# ETAG_v9_3b_EM4095.net
KiCad netlist of a schematic drawn in EAGLE
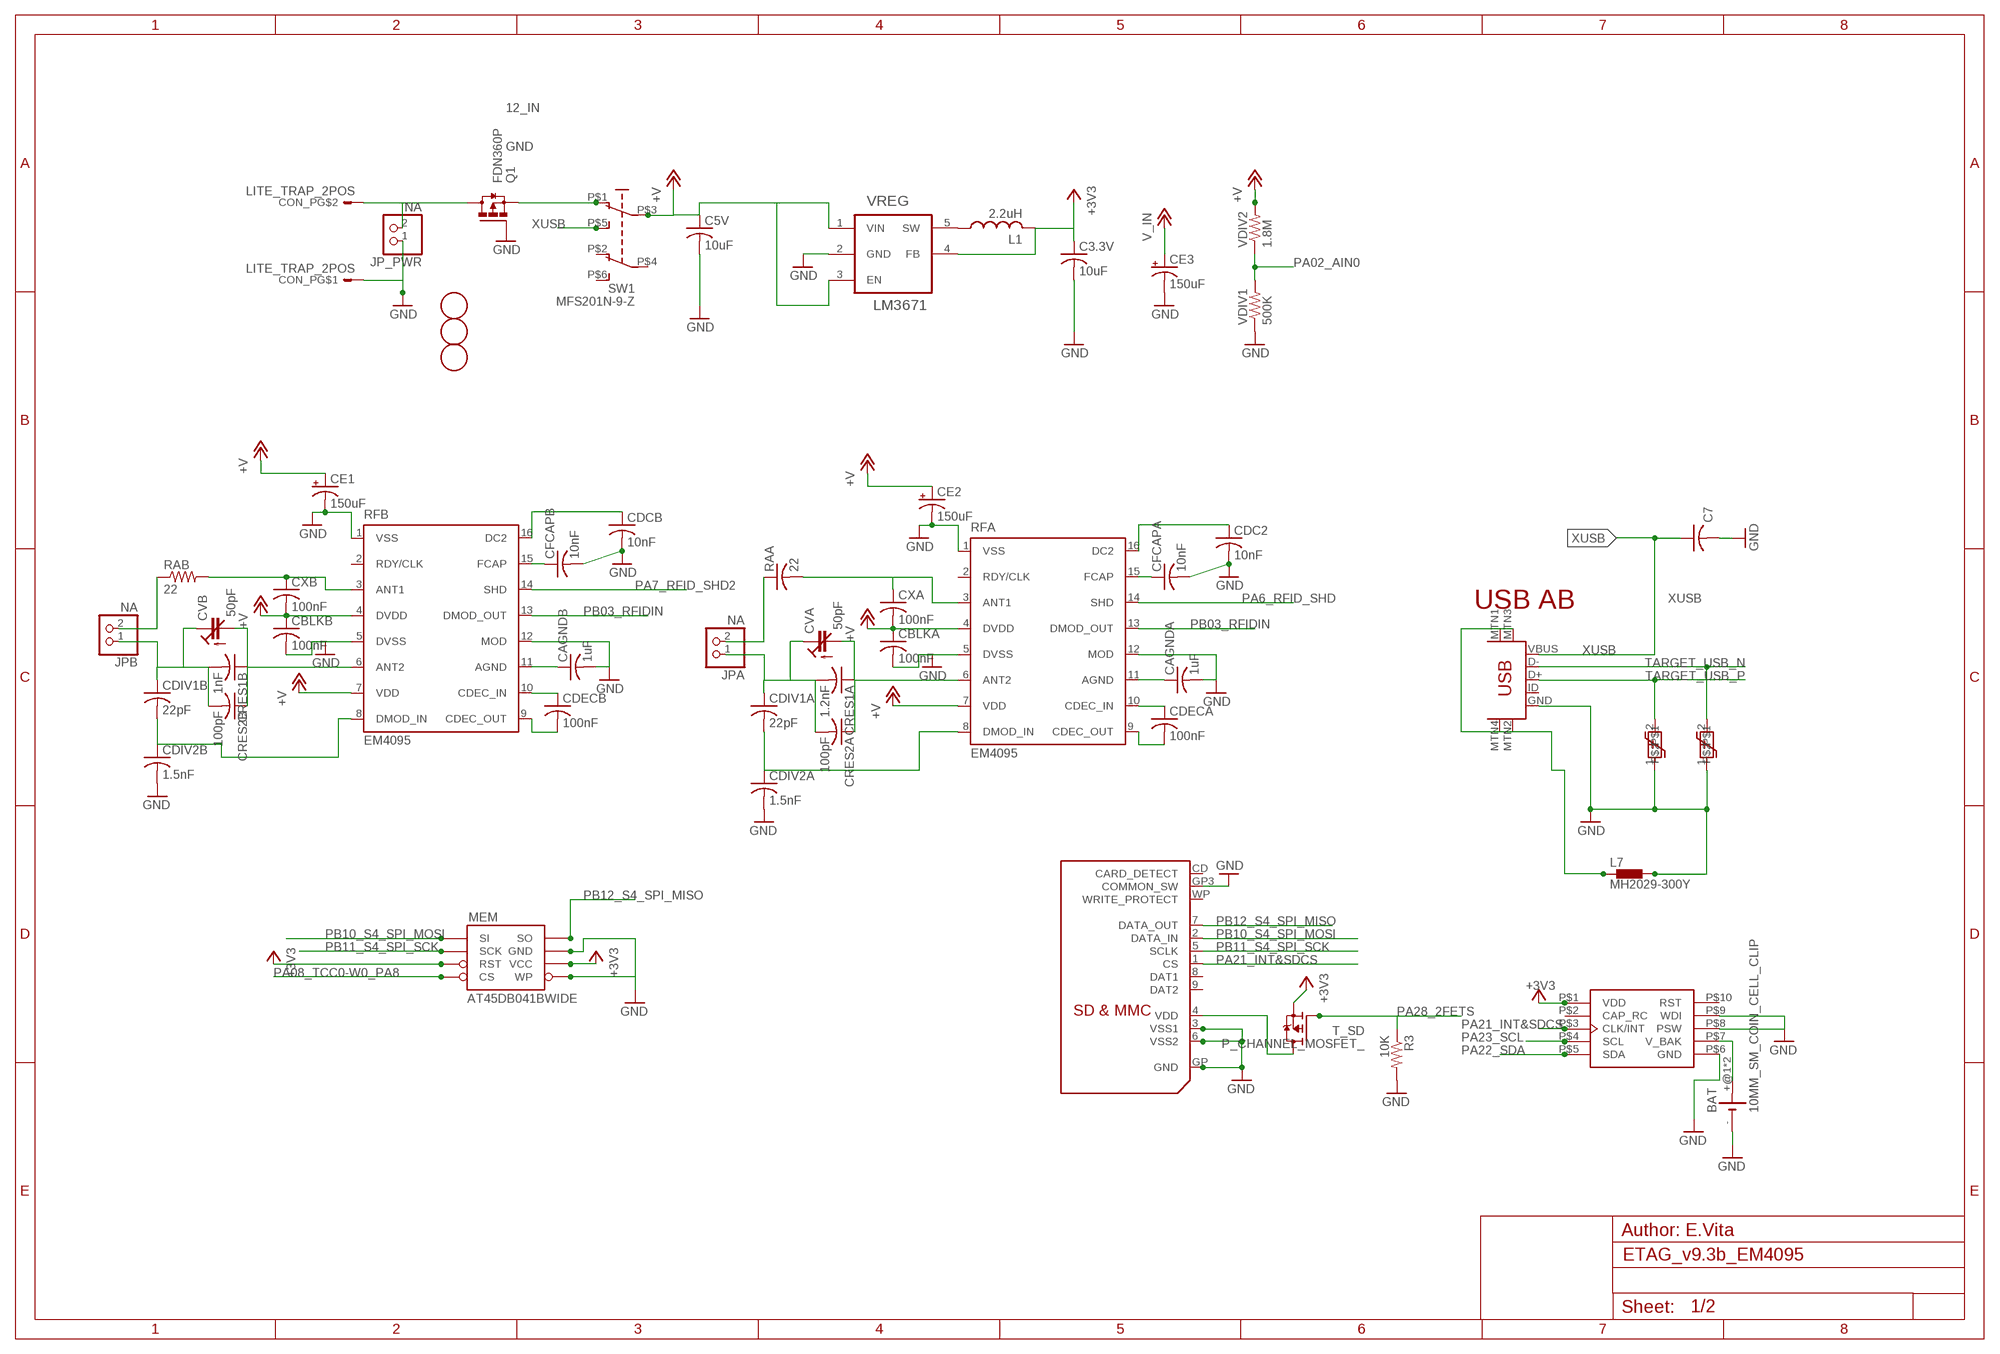
[diagram p0: schematic, sheet 1]
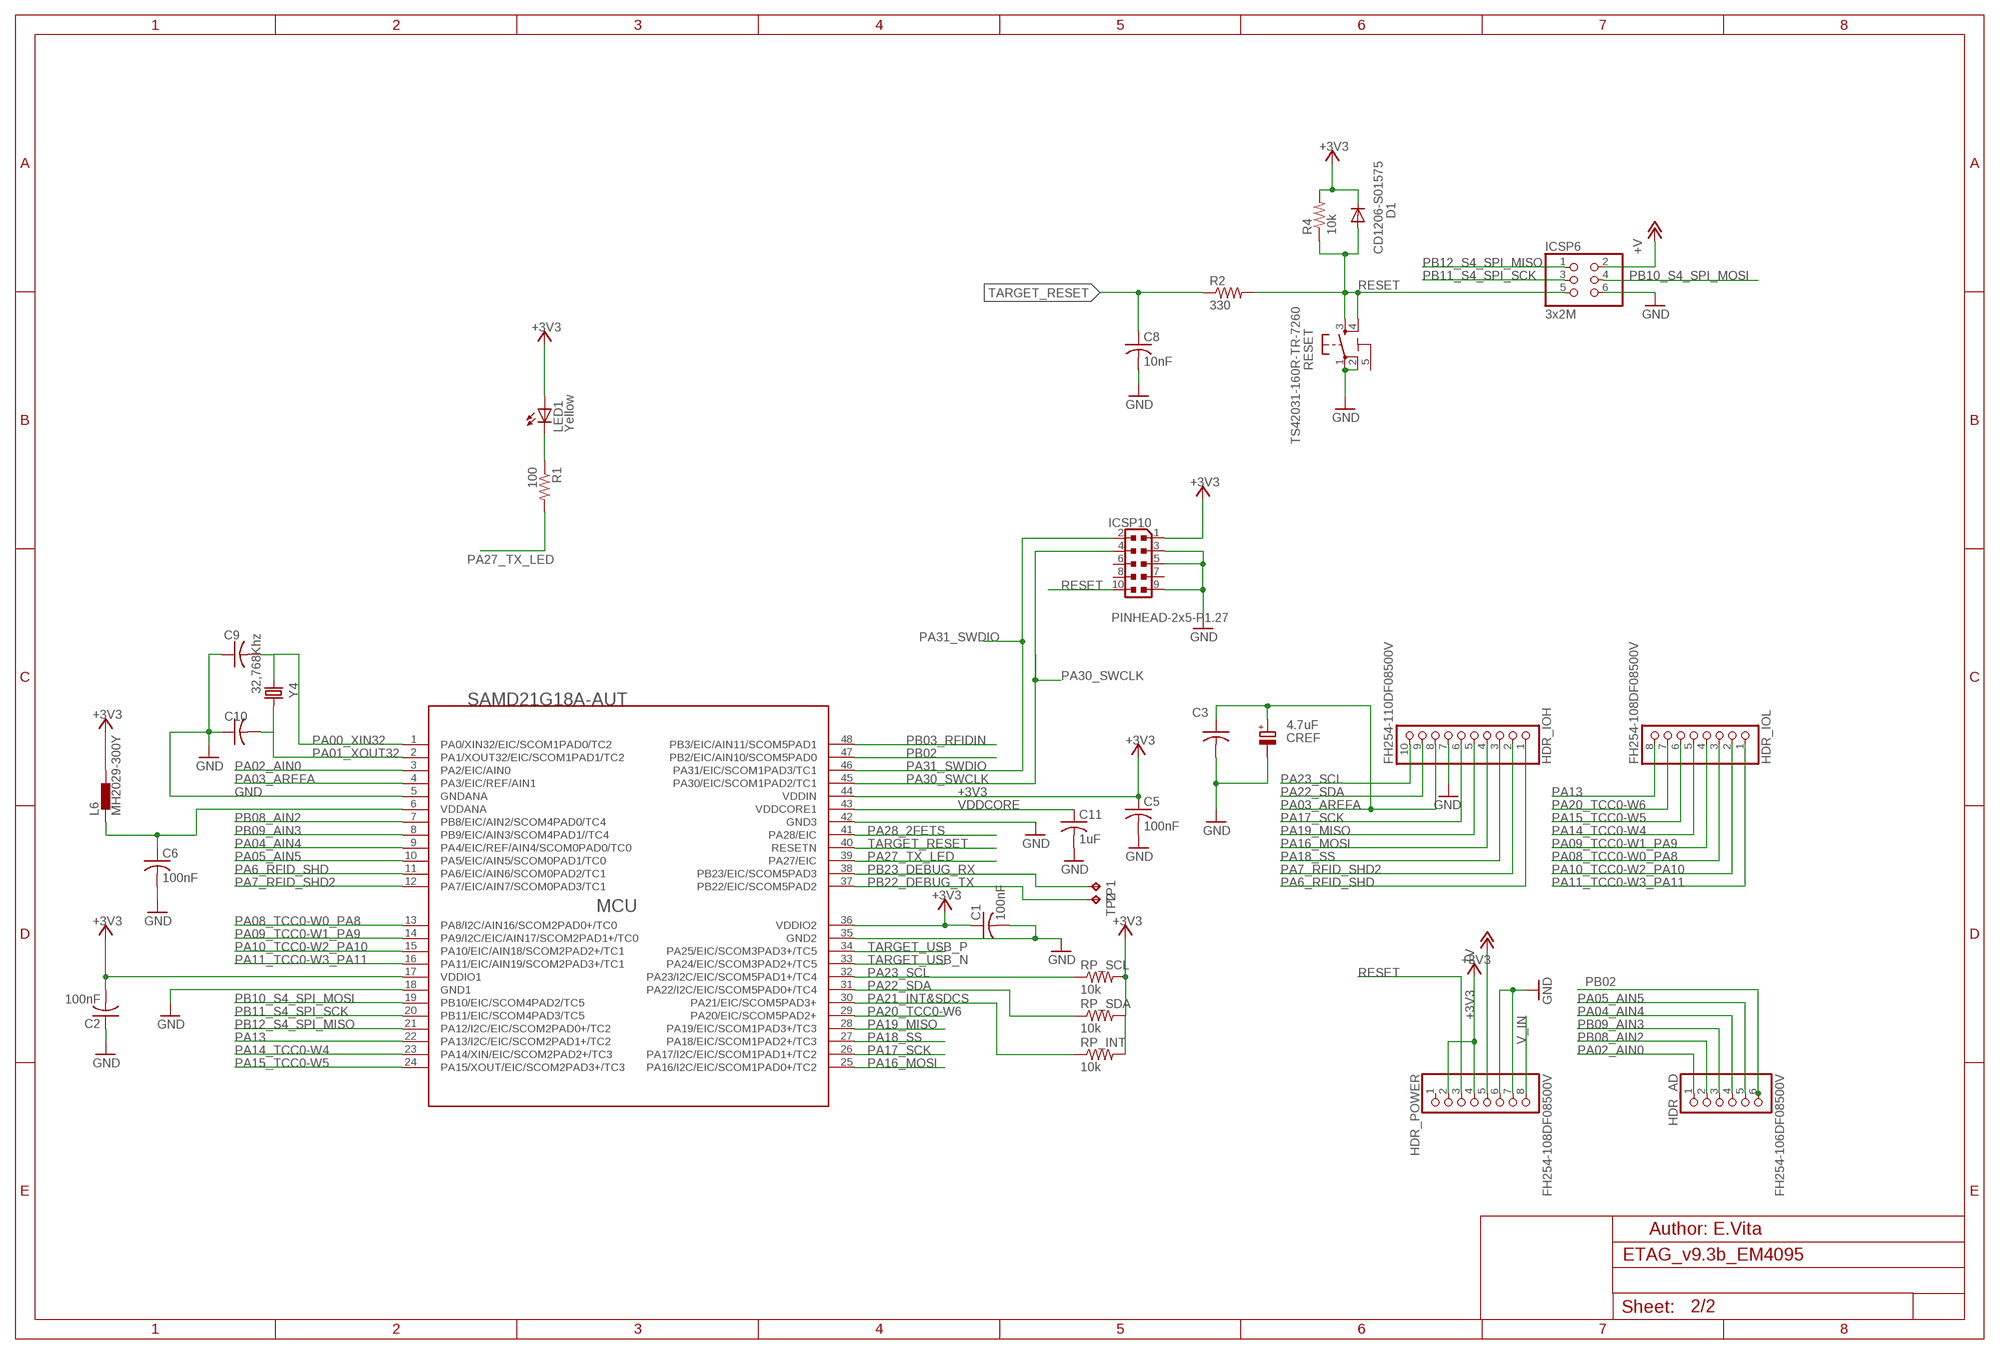
[diagram p1: schematic, sheet 2]

(export (version "E")
  (design (tool "Eeschema 10.0.6"))
  (components
    (comp (ref "C1")
      (value "100nF")
      (footprint "eagle-import:C0603-ROUND")
      (libsource (lib "eagle-import") (part "C-USROUND"))
    )
    (comp (ref "C2")
      (value "100nF")
      (footprint "eagle-import:C0603-ROUND")
      (libsource (lib "eagle-import") (part "C-USROUND"))
    )
    (comp (ref "C3")
      (value "100nF")
      (footprint "eagle-import:C0603-ROUND")
      (libsource (lib "eagle-import") (part "C-USROUND"))
    )
    (comp (ref "C5")
      (value "100nF")
      (footprint "eagle-import:C0603-ROUND")
      (libsource (lib "eagle-import") (part "C-USROUND"))
    )
    (comp (ref "C6")
      (value "100nF")
      (footprint "eagle-import:C0603-ROUND")
      (libsource (lib "eagle-import") (part "C-USROUND"))
    )
    (comp (ref "C8")
      (value "10nF")
      (footprint "eagle-import:C0603-ROUND")
      (libsource (lib "eagle-import") (part "C-USROUND"))
    )
    (comp (ref "C9")
      (value "22pF")
      (footprint "eagle-import:C0603-ROUND")
      (libsource (lib "eagle-import") (part "C-USROUND"))
    )
    (comp (ref "C10")
      (value "22pF")
      (footprint "eagle-import:C0603-ROUND")
      (libsource (lib "eagle-import") (part "C-USROUND"))
    )
    (comp (ref "C11")
      (value "1uF")
      (footprint "eagle-import:C0603-ROUND")
      (libsource (lib "eagle-import") (part "C-USROUND"))
    )
    (comp (ref "CREF")
      (value "4.7uF")
      (footprint "eagle-import:SMC_A")
      (fields (field (name "PART_NUMBER") "TAJA475M016RNJ"))
      (libsource (lib "eagle-import") (part "0474_TAJA475M016RNJ"))
    )
    (comp (ref "D1")
      (value "CD1206-S01575")
      (footprint "eagle-import:MINIMELF")
      (libsource (lib "eagle-import") (part "0012_CD1206-S01575"))
    )
    (comp (ref "HDR_AD")
      (value "FH254-106DF08500V")
      (footprint "eagle-import:1X06")
      (fields (field (name "PART_NUMBER") "20TW-535"))
      (libsource (lib "eagle-import") (part "1682_20TW-535_STD"))
    )
    (comp (ref "HDR_IOH")
      (value "FH254-110DF08500V")
      (footprint "eagle-import:1X10")
      (fields (field (name "PART_NUMBER") "20TW-537"))
      (libsource (lib "eagle-import") (part "1684_20TW-537"))
    )
    (comp (ref "HDR_IOL")
      (value "FH254-108DF08500V")
      (footprint "eagle-import:1X08")
      (fields (field (name "PART_NUMBER") "20TW-536"))
      (libsource (lib "eagle-import") (part "1683_20TW-536"))
    )
    (comp (ref "HDR_POWER")
      (value "FH254-108DF08500V")
      (footprint "eagle-import:1X08")
      (fields (field (name "PART_NUMBER") "20TW-536"))
      (libsource (lib "eagle-import") (part "1683_20TW-536"))
    )
    (comp (ref "ICSP6")
      (value "3x2M")
      (footprint "eagle-import:2X03")
      (fields (field (name "PART_NUMBER") "PH254-203DF118A00V"))
      (libsource (lib "eagle-import") (part "0114_PH254-203DF118A00V"))
    )
    (comp (ref "ICSP10")
      (value "PINHEAD-2x5-P1.27")
      (footprint "eagle-import:PINHEAD_2X05_127")
      (libsource (lib "eagle-import") (part "0171_PH127-205DF055G00AROUND-PADS"))
    )
    (comp (ref "L6")
      (value "MH2029-300Y")
      (footprint "eagle-import:C0805K")
      (libsource (lib "eagle-import") (part "BLM15H0805"))
    )
    (comp (ref "LED1")
      (value "Yellow")
      (footprint "eagle-import:CHIPLED_0805")
      (fields (field (name "PART_NUMBER") "KPT-2012YC"))
      (libsource (lib "eagle-import") (part "0044_KPT-2012YC"))
    )
    (comp (ref "MCU")
      (value "SAMD21G18A-AUT")
      (footprint "eagle-import:TQFP48-7X7")
      (libsource (lib "eagle-import") (part "1792_SAMD21G18A-AUT"))
    )
    (comp (ref "R1")
      (value "100")
      (footprint "eagle-import:C0603-ROUND")
      (libsource (lib "eagle-import") (part "R-US_ROUND"))
    )
    (comp (ref "R2")
      (value "330")
      (footprint "eagle-import:C0603-ROUND")
      (libsource (lib "eagle-import") (part "R-US_ROUND"))
    )
    (comp (ref "R4")
      (value "10k")
      (footprint "eagle-import:C0603-ROUND")
      (libsource (lib "eagle-import") (part "R-US_ROUND"))
    )
    (comp (ref "RESET")
      (value "TS42031-160R-TR-7260")
      (footprint "eagle-import:TS42")
      (fields (field (name "PART_NUMBER") "IT-1157AHNP-160G-G_GTR"))
      (libsource (lib "eagle-import") (part "0946_TS42031-160W-TR-7260"))
    )
    (comp (ref "RP_INT")
      (value "10k")
      (footprint "eagle-import:C0603-ROUND")
      (libsource (lib "eagle-import") (part "R-US_ROUND"))
    )
    (comp (ref "RP_SCL")
      (value "10k")
      (footprint "eagle-import:C0603-ROUND")
      (libsource (lib "eagle-import") (part "R-US_ROUND"))
    )
    (comp (ref "RP_SDA")
      (value "10k")
      (footprint "eagle-import:C0603-ROUND")
      (libsource (lib "eagle-import") (part "R-US_ROUND"))
    )
    (comp (ref "TP1")
      (value "TPTP15R")
      (footprint "eagle-import:TP15R")
      (libsource (lib "eagle-import") (part "TPTP15R"))
    )
    (comp (ref "TP2")
      (value "TPTP15R")
      (footprint "eagle-import:TP15R")
      (libsource (lib "eagle-import") (part "TPTP15R"))
    )
    (comp (ref "Y4")
      (value "32,768Khz")
      (footprint "eagle-import:RESONATOR_EPSON_FC_145")
      (fields (field (name "PART_NUMBER") "ABS07-32.768KHZ-T"))
      (libsource (lib "eagle-import") (part "0213_ABS07-32.768KHZ-T"))
    )
    (comp (ref "BAT")
      (value "10MM_SM_COIN_CELL_CLIP")
      (footprint "eagle-import:10MM_SM_COIN_CELL_CLIP")
      (libsource (lib "eagle-import") (part "10MM_SM_COIN_CELL_CLIP"))
    )
    (comp (ref "C3.3V")
      (value "10uF")
      (footprint "eagle-import:C0805")
      (libsource (lib "eagle-import") (part "C-USC0805"))
    )
    (comp (ref "C5V")
      (value "10uF")
      (footprint "eagle-import:C0805")
      (libsource (lib "eagle-import") (part "C-USC0805"))
    )
    (comp (ref "C7")
      (value "10nF")
      (footprint "eagle-import:C0603-ROUND")
      (libsource (lib "eagle-import") (part "C-USROUND"))
    )
    (comp (ref "CAGNDA")
      (value "1uF")
      (footprint "eagle-import:C0603-ROUND")
      (libsource (lib "eagle-import") (part "C-US"))
    )
    (comp (ref "CAGNDB")
      (value "1uF")
      (footprint "eagle-import:C0603-ROUND")
      (libsource (lib "eagle-import") (part "C-US"))
    )
    (comp (ref "CBLKA")
      (value "100nF")
      (footprint "eagle-import:C0603-ROUND")
      (libsource (lib "eagle-import") (part "C-US"))
    )
    (comp (ref "CBLKB")
      (value "100nF")
      (footprint "eagle-import:C0603-ROUND")
      (libsource (lib "eagle-import") (part "C-US"))
    )
    (comp (ref "CDC2")
      (value "10nF")
      (footprint "eagle-import:C0603-ROUND")
      (libsource (lib "eagle-import") (part "C-US"))
    )
    (comp (ref "CDCB")
      (value "10nF")
      (footprint "eagle-import:C0603-ROUND")
      (libsource (lib "eagle-import") (part "C-USROUND"))
    )
    (comp (ref "CDECA")
      (value "100nF")
      (footprint "eagle-import:C0603-ROUND")
      (libsource (lib "eagle-import") (part "C-US"))
    )
    (comp (ref "CDECB")
      (value "100nF")
      (footprint "eagle-import:C0603-ROUND")
      (libsource (lib "eagle-import") (part "C-US"))
    )
    (comp (ref "CDIV1A")
      (value "22pF")
      (footprint "eagle-import:C0603-ROUND")
      (libsource (lib "eagle-import") (part "C-US"))
    )
    (comp (ref "CDIV1B")
      (value "22pF")
      (footprint "eagle-import:C0603-ROUND")
      (libsource (lib "eagle-import") (part "C-US"))
    )
    (comp (ref "CDIV2A")
      (value "1.5nF")
      (footprint "eagle-import:C0603-ROUND")
      (libsource (lib "eagle-import") (part "C-USROUND"))
    )
    (comp (ref "CDIV2B")
      (value "1.5nF")
      (footprint "eagle-import:C0603-ROUND")
      (libsource (lib "eagle-import") (part "C-US"))
    )
    (comp (ref "CE1")
      (value "150uF")
      (footprint "eagle-import:E2-5")
      (libsource (lib "eagle-import") (part "CPOL-USE2-5"))
    )
    (comp (ref "CE2")
      (value "150uF")
      (footprint "eagle-import:E2-5")
      (libsource (lib "eagle-import") (part "CPOL-USE2-5"))
    )
    (comp (ref "CE3")
      (value "150uF")
      (footprint "eagle-import:E2-5")
      (libsource (lib "eagle-import") (part "CPOL-USE2-5"))
    )
    (comp (ref "CFCAPA")
      (value "10nF")
      (footprint "eagle-import:C0603-ROUND")
      (libsource (lib "eagle-import") (part "C-USROUND"))
    )
    (comp (ref "CFCAPB")
      (value "10nF")
      (footprint "eagle-import:C0603-ROUND")
      (libsource (lib "eagle-import") (part "C-US"))
    )
    (comp (ref "CON_P")
      (value "LITE_TRAP_2POS")
      (footprint "eagle-import:LITE_TRAP_MINI")
      (libsource (lib "eagle-import") (part "LITE_TRAP_2POS"))
    )
    (comp (ref "CRES1A")
      (value "1.2nF")
      (footprint "eagle-import:C0603-ROUND")
      (libsource (lib "eagle-import") (part "C-USROUND"))
    )
    (comp (ref "CRES1B")
      (value "1nF")
      (footprint "eagle-import:C0603-ROUND")
      (libsource (lib "eagle-import") (part "C-US"))
    )
    (comp (ref "CRES2A")
      (value "100pF")
      (footprint "eagle-import:C0603-ROUND")
      (libsource (lib "eagle-import") (part "C-US"))
    )
    (comp (ref "CRES2B")
      (value "100pF")
      (footprint "eagle-import:C0603-ROUND")
      (libsource (lib "eagle-import") (part "C-US"))
    )
    (comp (ref "CVA")
      (value "50pF")
      (footprint "eagle-import:CTRIM3018_11")
      (libsource (lib "eagle-import") (part "C-TRIMM3018_11"))
    )
    (comp (ref "CVB")
      (value "50pF")
      (footprint "eagle-import:CTRIM3018_11")
      (libsource (lib "eagle-import") (part "C-TRIMM3018_11"))
    )
    (comp (ref "CXA")
      (value "100nF")
      (footprint "eagle-import:C0603-ROUND")
      (libsource (lib "eagle-import") (part "C-US"))
    )
    (comp (ref "CXB")
      (value "100nF")
      (footprint "eagle-import:C0603-ROUND")
      (libsource (lib "eagle-import") (part "C-US"))
    )
    (comp (ref "FD1")
      (value "FIDUCIALMOUNT")
      (footprint "eagle-import:FIDUCIA-MOUNT")
      (libsource (lib "eagle-import") (part "FIDUCIALMOUNT"))
    )
    (comp (ref "FD2")
      (value "FIDUCIALMOUNT")
      (footprint "eagle-import:FIDUCIA-MOUNT")
      (libsource (lib "eagle-import") (part "FIDUCIALMOUNT"))
    )
    (comp (ref "FD3")
      (value "FIDUCIALMOUNT")
      (footprint "eagle-import:FIDUCIA-MOUNT")
      (libsource (lib "eagle-import") (part "FIDUCIALMOUNT"))
    )
    (comp (ref "JPA")
      (value "NA")
      (footprint "eagle-import:1X02")
      (libsource (lib "eagle-import") (part "PINHD-1X2"))
    )
    (comp (ref "JPB")
      (value "NA")
      (footprint "eagle-import:1X02")
      (libsource (lib "eagle-import") (part "PINHD-1X2"))
    )
    (comp (ref "JP_PWR")
      (value "NA")
      (footprint "eagle-import:1X02")
      (libsource (lib "eagle-import") (part "PINHD-1X2"))
    )
    (comp (ref "L1")
      (value "2.2uH")
      (footprint "eagle-import:SMT_COIL_INDUCTOR_4X4MM")
      (libsource (lib "eagle-import") (part "L-US4X4"))
    )
    (comp (ref "L7")
      (value "MH2029-300Y")
      (footprint "eagle-import:C0805K")
      (libsource (lib "eagle-import") (part "BLM15H0805"))
    )
    (comp (ref "MEM")
      (value "AT45DB041BWIDE")
      (footprint "eagle-import:SO08WIDE")
      (libsource (lib "eagle-import") (part "AT45DB041BWIDE"))
    )
    (comp (ref "Q1")
      (value "FDN360P")
      (footprint "eagle-import:SUPER-SOT3")
      (libsource (lib "eagle-import") (part "FDN360P"))
    )
    (comp (ref "R3")
      (value "10K")
      (footprint "eagle-import:C0603-ROUND")
      (libsource (lib "eagle-import") (part "R-US_ROUND"))
    )
    (comp (ref "RAA")
      (value "22")
      (footprint "eagle-import:C0805")
      (libsource (lib "eagle-import") (part "C-USC0805"))
    )
    (comp (ref "RAB")
      (value "22")
      (footprint "eagle-import:R0805")
      (libsource (lib "eagle-import") (part "R-US_R0805"))
    )
    (comp (ref "RFA")
      (value "EM4095")
      (footprint "eagle-import:SO16")
      (libsource (lib "eagle-import") (part "EM4095"))
    )
    (comp (ref "RFB")
      (value "EM4095")
      (footprint "eagle-import:SO16")
      (libsource (lib "eagle-import") (part "EM4095"))
    )
    (comp (ref "RTC")
      (value "MC-RTC-RV-1805-C3-I2C")
      (footprint "eagle-import:MC-RTC-C3")
      (libsource (lib "eagle-import") (part "MC-RTC-RV-1805-C3-I2C"))
    )
    (comp (ref "SD")
      (value "SDMMC06132")
      (footprint "eagle-import:06132")
      (libsource (lib "eagle-import") (part "SDMMC06132"))
    )
    (comp (ref "SW1")
      (value "MFS201N-9-Z")
      (footprint "eagle-import:MFS201N-9-Z")
      (libsource (lib "eagle-import") (part "MFS201N-9-Z"))
    )
    (comp (ref "T_SD")
      (value "P_CHANNEL_MOSFET_")
      (footprint "eagle-import:SOT23")
      (libsource (lib "eagle-import") (part "P_CHANNEL_MOSFET_"))
    )
    (comp (ref "USB")
      (value "USB-MINIB-5PIN")
      (footprint "eagle-import:USB-MINIB")
      (libsource (lib "eagle-import") (part "USB-MINIB-5PIN"))
    )
    (comp (ref "VDIV1")
      (value "500K")
      (footprint "eagle-import:C0603-ROUND")
      (libsource (lib "eagle-import") (part "R-US_ROUND"))
    )
    (comp (ref "VDIV2")
      (value "1.8M")
      (footprint "eagle-import:C0603-ROUND")
      (libsource (lib "eagle-import") (part "R-US_ROUND"))
    )
    (comp (ref "VREG")
      (value "LM3671")
      (footprint "eagle-import:SOT23-5L")
      (libsource (lib "eagle-import") (part "LM3671_SWITCHING_REGSOT23"))
    )
    (comp (ref "Z5")
      (value "ESD_SUPRESSOR")
      (footprint "eagle-import:C0603-ROUND")
      (libsource (lib "eagle-import") (part "ESD_SUPRESSOR"))
    )
    (comp (ref "Z6")
      (value "ESD_SUPRESSOR")
      (footprint "eagle-import:C0603-ROUND")
      (libsource (lib "eagle-import") (part "ESD_SUPRESSOR"))
    )
  )
  (nets
    (net (code "1") (name "+3V3") (class "Default")
      (node (ref "C1") (pin "1") (pinfunction "1_1") (pintype "passive"))
      (node (ref "C2") (pin "2") (pinfunction "2_2") (pintype "passive"))
      (node (ref "C3.3V") (pin "1") (pinfunction "1_1") (pintype "passive"))
      (node (ref "C5") (pin "1") (pinfunction "1_1") (pintype "passive"))
      (node (ref "D1") (pin "C") (pinfunction "C_C") (pintype "passive"))
      (node (ref "HDR_POWER") (pin "2") (pinfunction "2_2") (pintype "passive"))
      (node (ref "HDR_POWER") (pin "4") (pinfunction "4_4") (pintype "passive"))
      (node (ref "ICSP10") (pin "1") (pinfunction "1_1") (pintype "passive"))
      (node (ref "L1") (pin "P$2") (pinfunction "2_P$2") (pintype "passive"))
      (node (ref "L6") (pin "2") (pinfunction "2_2") (pintype "passive"))
      (node (ref "LED1") (pin "A") (pinfunction "A_A") (pintype "passive"))
      (node (ref "MCU") (pin "17") (pinfunction "VDDIO1_17") (pintype "power_in"))
      (node (ref "MCU") (pin "36") (pinfunction "VDDIO2_36") (pintype "power_in"))
      (node (ref "MCU") (pin "44") (pinfunction "VDDIN_44") (pintype "power_in"))
      (node (ref "MEM") (pin "3") (pinfunction "RST_3") (pintype "bidirectional"))
      (node (ref "MEM") (pin "6") (pinfunction "VCC_6") (pintype "bidirectional"))
      (node (ref "R4") (pin "2") (pinfunction "2_2") (pintype "passive"))
      (node (ref "RP_INT") (pin "2") (pinfunction "2_2") (pintype "passive"))
      (node (ref "RP_SCL") (pin "2") (pinfunction "2_2") (pintype "passive"))
      (node (ref "RP_SDA") (pin "2") (pinfunction "2_2") (pintype "passive"))
      (node (ref "RTC") (pin "P$1") (pinfunction "VDD_P$1") (pintype "power_in"))
      (node (ref "T_SD") (pin "2") (pinfunction "S_2") (pintype "passive"))
      (node (ref "VREG") (pin "4") (pinfunction "FB_4") (pintype "power_in"))
    )
    (net (code "2") (name "5-GND") (class "Default")
      (node (ref "RESET") (pin "5") (pinfunction "5-GND_5") (pintype "power_in"))
    )
    (net (code "3") (name "12_IN") (class "Default")
      (node (ref "CON_P") (pin "P$3") (pinfunction "S_P$3") (pintype "passive"))
      (node (ref "CON_P") (pin "P$4") (pinfunction "S_P$4") (pintype "passive"))
      (node (ref "JP_PWR") (pin "2") (pinfunction "2_2") (pintype "passive"))
      (node (ref "Q1") (pin "3") (pinfunction "D_3") (pintype "passive"))
    )
    (net (code "4") (name "GND") (class "Default")
      (node (ref "BAT") (pin "-") (pinfunction "-_-") (pintype "passive"))
      (node (ref "C1") (pin "2") (pinfunction "2_2") (pintype "passive"))
      (node (ref "C10") (pin "1") (pinfunction "1_1") (pintype "passive"))
      (node (ref "C11") (pin "2") (pinfunction "2_2") (pintype "passive"))
      (node (ref "C2") (pin "1") (pinfunction "1_1") (pintype "passive"))
      (node (ref "C3") (pin "2") (pinfunction "2_2") (pintype "passive"))
      (node (ref "C3.3V") (pin "2") (pinfunction "2_2") (pintype "passive"))
      (node (ref "C5") (pin "2") (pinfunction "2_2") (pintype "passive"))
      (node (ref "C5V") (pin "2") (pinfunction "2_2") (pintype "passive"))
      (node (ref "C6") (pin "2") (pinfunction "2_2") (pintype "passive"))
      (node (ref "C7") (pin "2") (pinfunction "2_2") (pintype "passive"))
      (node (ref "C8") (pin "2") (pinfunction "2_2") (pintype "passive"))
      (node (ref "C9") (pin "1") (pinfunction "1_1") (pintype "passive"))
      (node (ref "CAGNDA") (pin "2") (pinfunction "2_2") (pintype "passive"))
      (node (ref "CAGNDB") (pin "2") (pinfunction "2_2") (pintype "passive"))
      (node (ref "CBLKA") (pin "2") (pinfunction "2_2") (pintype "passive"))
      (node (ref "CBLKB") (pin "2") (pinfunction "2_2") (pintype "passive"))
      (node (ref "CDC2") (pin "2") (pinfunction "2_2") (pintype "passive"))
      (node (ref "CDCB") (pin "2") (pinfunction "2_2") (pintype "passive"))
      (node (ref "CDIV2A") (pin "2") (pinfunction "2_2") (pintype "passive"))
      (node (ref "CDIV2B") (pin "2") (pinfunction "2_2") (pintype "passive"))
      (node (ref "CE1") (pin "-") (pinfunction "-_-") (pintype "passive"))
      (node (ref "CE2") (pin "-") (pinfunction "-_-") (pintype "passive"))
      (node (ref "CE3") (pin "-") (pinfunction "-_-") (pintype "passive"))
      (node (ref "CFCAPA") (pin "2") (pinfunction "2_2") (pintype "passive"))
      (node (ref "CFCAPB") (pin "2") (pinfunction "2_2") (pintype "passive"))
      (node (ref "CON_P") (pin "P$1") (pinfunction "S_P$1") (pintype "passive"))
      (node (ref "CON_P") (pin "P$2") (pinfunction "S_P$2") (pintype "passive"))
      (node (ref "CREF") (pin "-") (pinfunction "-_-") (pintype "passive"))
      (node (ref "HDR_IOH") (pin "7") (pinfunction "7_7") (pintype "passive"))
      (node (ref "HDR_POWER") (pin "6") (pinfunction "6_6") (pintype "passive"))
      (node (ref "HDR_POWER") (pin "7") (pinfunction "7_7") (pintype "passive"))
      (node (ref "ICSP10") (pin "3") (pinfunction "3_3") (pintype "passive"))
      (node (ref "ICSP10") (pin "5") (pinfunction "5_5") (pintype "passive"))
      (node (ref "ICSP10") (pin "9") (pinfunction "9_9") (pintype "passive"))
      (node (ref "ICSP6") (pin "6") (pinfunction "6_6") (pintype "passive"))
      (node (ref "JP_PWR") (pin "1") (pinfunction "1_1") (pintype "passive"))
      (node (ref "L7") (pin "2") (pinfunction "2_2") (pintype "passive"))
      (node (ref "MCU") (pin "18") (pinfunction "GND1_18") (pintype "power_in"))
      (node (ref "MCU") (pin "35") (pinfunction "GND2_35") (pintype "power_in"))
      (node (ref "MCU") (pin "42") (pinfunction "GND3_42") (pintype "power_in"))
      (node (ref "MCU") (pin "5") (pinfunction "GNDANA_5") (pintype "power_in"))
      (node (ref "MEM") (pin "5") (pinfunction "WP_5") (pintype "bidirectional"))
      (node (ref "MEM") (pin "7") (pinfunction "GND_7") (pintype "bidirectional"))
      (node (ref "Q1") (pin "1") (pinfunction "G_1") (pintype "passive"))
      (node (ref "R3") (pin "2") (pinfunction "2_2") (pintype "passive"))
      (node (ref "RESET") (pin "1") (pinfunction "1_1") (pintype "passive"))
      (node (ref "RESET") (pin "2") (pinfunction "2_2") (pintype "passive"))
      (node (ref "RFA") (pin "1") (pinfunction "VSS_1") (pintype "power_in"))
      (node (ref "RFA") (pin "12") (pinfunction "MOD_12") (pintype "input"))
      (node (ref "RFA") (pin "5") (pinfunction "DVSS_5") (pintype "power_in"))
      (node (ref "RFB") (pin "1") (pinfunction "VSS_1") (pintype "power_in"))
      (node (ref "RFB") (pin "12") (pinfunction "MOD_12") (pintype "input"))
      (node (ref "RFB") (pin "5") (pinfunction "DVSS_5") (pintype "power_in"))
      (node (ref "RTC") (pin "P$6") (pinfunction "GND_P$6") (pintype "power_in"))
      (node (ref "RTC") (pin "P$8") (pinfunction "PSW_P$8") (pintype "bidirectional"))
      (node (ref "RTC") (pin "P$9") (pinfunction "WDI_P$9") (pintype "bidirectional"))
      (node (ref "SD") (pin "3") (pinfunction "VSS1_3") (pintype "power_in"))
      (node (ref "SD") (pin "6") (pinfunction "VSS2_6") (pintype "power_in"))
      (node (ref "SD") (pin "GP") (pinfunction "GND_GP") (pintype "power_in"))
      (node (ref "SD") (pin "GP3") (pinfunction "COMMON_SW_GP3") (pintype "passive"))
      (node (ref "USB") (pin "GND") (pinfunction "GND_GND") (pintype "bidirectional"))
      (node (ref "VDIV1") (pin "1") (pinfunction "1_1") (pintype "passive"))
      (node (ref "VREG") (pin "2") (pinfunction "GND_2") (pintype "passive"))
      (node (ref "Z5") (pin "1") (pinfunction "P$1_1") (pintype "bidirectional"))
      (node (ref "Z6") (pin "1") (pinfunction "P$1_1") (pintype "bidirectional"))
    )
    (net (code "5") (name "Net-(CVA-A)") (class "Default")
      (node (ref "CRES1A") (pin "1") (pinfunction "1_1") (pintype "passive"))
      (node (ref "CRES2A") (pin "1") (pinfunction "1_1") (pintype "passive"))
      (node (ref "CVA") (pin "-") (pinfunction "A_-") (pintype "passive"))
      (node (ref "RFA") (pin "6") (pinfunction "ANT2_6") (pintype "passive"))
    )
    (net (code "6") (name "Net-(CVA-E)") (class "Default")
      (node (ref "CDIV1A") (pin "1") (pinfunction "1_1") (pintype "passive"))
      (node (ref "CRES1A") (pin "2") (pinfunction "2_2") (pintype "passive"))
      (node (ref "CRES2A") (pin "2") (pinfunction "2_2") (pintype "passive"))
      (node (ref "CVA") (pin "+") (pinfunction "E_+") (pintype "passive"))
      (node (ref "JPA") (pin "1") (pinfunction "1_1") (pintype "passive"))
    )
    (net (code "7") (name "Net-(CVB-A)") (class "Default")
      (node (ref "CRES1B") (pin "1") (pinfunction "1_1") (pintype "passive"))
      (node (ref "CRES2B") (pin "1") (pinfunction "1_1") (pintype "passive"))
      (node (ref "CVB") (pin "-") (pinfunction "A_-") (pintype "passive"))
      (node (ref "RFB") (pin "6") (pinfunction "ANT2_6") (pintype "passive"))
    )
    (net (code "8") (name "Net-(CVB-E)") (class "Default")
      (node (ref "CDIV1B") (pin "1") (pinfunction "1_1") (pintype "passive"))
      (node (ref "CRES1B") (pin "2") (pinfunction "2_2") (pintype "passive"))
      (node (ref "CRES2B") (pin "2") (pinfunction "2_2") (pintype "passive"))
      (node (ref "CVB") (pin "+") (pinfunction "E_+") (pintype "passive"))
      (node (ref "JPB") (pin "1") (pinfunction "1_1") (pintype "passive"))
    )
    (net (code "9") (name "Net-(JPA-Pad2)") (class "Default")
      (node (ref "JPA") (pin "2") (pinfunction "2_2") (pintype "passive"))
      (node (ref "RAA") (pin "1") (pinfunction "1_1") (pintype "passive"))
    )
    (net (code "10") (name "Net-(JPB-Pad2)") (class "Default")
      (node (ref "JPB") (pin "2") (pinfunction "2_2") (pintype "passive"))
      (node (ref "RAB") (pin "1") (pinfunction "1_1") (pintype "passive"))
    )
    (net (code "11") (name "Net-(L1-1)") (class "Default")
      (node (ref "L1") (pin "P$1") (pinfunction "1_P$1") (pintype "passive"))
      (node (ref "VREG") (pin "5") (pinfunction "SW_5") (pintype "power_in"))
    )
    (net (code "12") (name "Net-(LED1-PadC)") (class "Default")
      (node (ref "LED1") (pin "C") (pinfunction "C_C") (pintype "passive"))
      (node (ref "R1") (pin "1") (pinfunction "1_1") (pintype "passive"))
    )
    (net (code "13") (name "Net-(MCU-VDDANA)") (class "Default")
      (node (ref "C6") (pin "1") (pinfunction "1_1") (pintype "passive"))
      (node (ref "L6") (pin "1") (pinfunction "1_1") (pintype "passive"))
      (node (ref "MCU") (pin "6") (pinfunction "VDDANA_6") (pintype "power_in"))
    )
    (net (code "14") (name "Net-(Q1-S)") (class "Default")
      (node (ref "Q1") (pin "2") (pinfunction "S_2") (pintype "passive"))
      (node (ref "SW1") (pin "P$1") (pinfunction "O_P$1") (pintype "passive"))
    )
    (net (code "15") (name "Net-(RFA-AGND)") (class "Default")
      (node (ref "CAGNDA") (pin "1") (pinfunction "1_1") (pintype "passive"))
      (node (ref "RFA") (pin "11") (pinfunction "AGND_11") (pintype "power_in"))
    )
    (net (code "16") (name "Net-(RFA-ANT1)") (class "Default")
      (node (ref "CXA") (pin "1") (pinfunction "1_1") (pintype "passive"))
      (node (ref "RAA") (pin "2") (pinfunction "2_2") (pintype "passive"))
      (node (ref "RFA") (pin "3") (pinfunction "ANT1_3") (pintype "passive"))
    )
    (net (code "17") (name "Net-(RFA-CDEC_IN)") (class "Default")
      (node (ref "CDECA") (pin "1") (pinfunction "1_1") (pintype "passive"))
      (node (ref "RFA") (pin "10") (pinfunction "CDEC_IN_10") (pintype "input"))
    )
    (net (code "18") (name "Net-(RFA-CDEC_OUT)") (class "Default")
      (node (ref "CDECA") (pin "2") (pinfunction "2_2") (pintype "passive"))
      (node (ref "RFA") (pin "9") (pinfunction "CDEC_OUT_9") (pintype "output"))
    )
    (net (code "19") (name "Net-(RFA-DC2)") (class "Default")
      (node (ref "CDC2") (pin "1") (pinfunction "1_1") (pintype "passive"))
      (node (ref "RFA") (pin "16") (pinfunction "DC2_16") (pintype "passive"))
    )
    (net (code "20") (name "Net-(RFA-DMOD_IN)") (class "Default")
      (node (ref "CDIV1A") (pin "2") (pinfunction "2_2") (pintype "passive"))
      (node (ref "CDIV2A") (pin "1") (pinfunction "1_1") (pintype "passive"))
      (node (ref "RFA") (pin "8") (pinfunction "DMOD_IN_8") (pintype "input"))
    )
    (net (code "21") (name "Net-(RFA-FCAP)") (class "Default")
      (node (ref "CFCAPA") (pin "1") (pinfunction "1_1") (pintype "passive"))
      (node (ref "RFA") (pin "15") (pinfunction "FCAP_15") (pintype "passive"))
    )
    (net (code "22") (name "Net-(RFB-AGND)") (class "Default")
      (node (ref "CAGNDB") (pin "1") (pinfunction "1_1") (pintype "passive"))
      (node (ref "RFB") (pin "11") (pinfunction "AGND_11") (pintype "power_in"))
    )
    (net (code "23") (name "Net-(RFB-ANT1)") (class "Default")
      (node (ref "CXB") (pin "1") (pinfunction "1_1") (pintype "passive"))
      (node (ref "RAB") (pin "2") (pinfunction "2_2") (pintype "passive"))
      (node (ref "RFB") (pin "3") (pinfunction "ANT1_3") (pintype "passive"))
    )
    (net (code "24") (name "Net-(RFB-CDEC_IN)") (class "Default")
      (node (ref "CDECB") (pin "1") (pinfunction "1_1") (pintype "passive"))
      (node (ref "RFB") (pin "10") (pinfunction "CDEC_IN_10") (pintype "input"))
    )
    (net (code "25") (name "Net-(RFB-CDEC_OUT)") (class "Default")
      (node (ref "CDECB") (pin "2") (pinfunction "2_2") (pintype "passive"))
      (node (ref "RFB") (pin "9") (pinfunction "CDEC_OUT_9") (pintype "output"))
    )
    (net (code "26") (name "Net-(RFB-DC2)") (class "Default")
      (node (ref "CDCB") (pin "1") (pinfunction "1_1") (pintype "passive"))
      (node (ref "RFB") (pin "16") (pinfunction "DC2_16") (pintype "passive"))
    )
    (net (code "27") (name "Net-(RFB-DMOD_IN)") (class "Default")
      (node (ref "CDIV1B") (pin "2") (pinfunction "2_2") (pintype "passive"))
      (node (ref "CDIV2B") (pin "1") (pinfunction "1_1") (pintype "passive"))
      (node (ref "RFB") (pin "8") (pinfunction "DMOD_IN_8") (pintype "input"))
    )
    (net (code "28") (name "Net-(RFB-FCAP)") (class "Default")
      (node (ref "CFCAPB") (pin "1") (pinfunction "1_1") (pintype "passive"))
      (node (ref "RFB") (pin "15") (pinfunction "FCAP_15") (pintype "passive"))
    )
    (net (code "29") (name "Net-(RTC-V_BAK)") (class "Default")
      (node (ref "BAT") (pin "+@1") (pinfunction "+_+@1") (pintype "passive"))
      (node (ref "BAT") (pin "+@2") (pinfunction "+_+@2") (pintype "passive"))
      (node (ref "RTC") (pin "P$7") (pinfunction "V_BAK_P$7") (pintype "power_in"))
    )
    (net (code "30") (name "Net-(SD-VDD)") (class "Default")
      (node (ref "SD") (pin "4") (pinfunction "VDD_4") (pintype "power_in"))
      (node (ref "T_SD") (pin "3") (pinfunction "D_3") (pintype "passive"))
    )
    (net (code "31") (name "Net-(USB-MTN1)") (class "Default")
      (node (ref "L7") (pin "1") (pinfunction "1_1") (pintype "passive"))
      (node (ref "USB") (pin "MTN1") (pinfunction "MTN2_MTN1") (pintype "bidirectional"))
      (node (ref "USB") (pin "MTN2") (pinfunction "MTN3_MTN2") (pintype "bidirectional"))
      (node (ref "USB") (pin "MTN3") (pinfunction "MTN1_MTN3") (pintype "bidirectional"))
      (node (ref "USB") (pin "MTN4") (pinfunction "MTN4_MTN4") (pintype "bidirectional"))
    )
    (net (code "32") (name "PA00_XIN32") (class "Default")
      (node (ref "C9") (pin "2") (pinfunction "2_2") (pintype "passive"))
      (node (ref "MCU") (pin "1") (pinfunction "PA0/XIN32/EIC/SCOM1PAD0/TC2_1") (pintype "bidirectional"))
      (node (ref "Y4") (pin "P$1") (pinfunction "1_P$1") (pintype "bidirectional"))
    )
    (net (code "33") (name "PA01_XOUT32") (class "Default")
      (node (ref "C10") (pin "2") (pinfunction "2_2") (pintype "passive"))
      (node (ref "MCU") (pin "2") (pinfunction "PA1/XOUT32/EIC/SCOM1PAD1/TC2_2") (pintype "bidirectional"))
      (node (ref "Y4") (pin "P$2") (pinfunction "2_P$2") (pintype "bidirectional"))
    )
    (net (code "34") (name "PA02_AIN0") (class "Default")
      (node (ref "HDR_AD") (pin "1") (pinfunction "1_1") (pintype "passive"))
      (node (ref "MCU") (pin "3") (pinfunction "PA2/EIC/AIN0_3") (pintype "bidirectional"))
      (node (ref "VDIV1") (pin "2") (pinfunction "2_2") (pintype "passive"))
      (node (ref "VDIV2") (pin "1") (pinfunction "1_1") (pintype "passive"))
    )
    (net (code "35") (name "PA03_AREFA") (class "Default")
      (node (ref "C3") (pin "1") (pinfunction "1_1") (pintype "passive"))
      (node (ref "CREF") (pin "+") (pinfunction "+_+") (pintype "passive"))
      (node (ref "HDR_IOH") (pin "8") (pinfunction "8_8") (pintype "passive"))
      (node (ref "MCU") (pin "4") (pinfunction "PA3/EIC/REF/AIN1_4") (pintype "bidirectional"))
    )
    (net (code "36") (name "PA04_AIN4") (class "Default")
      (node (ref "HDR_AD") (pin "4") (pinfunction "4_4") (pintype "passive"))
      (node (ref "MCU") (pin "9") (pinfunction "PA4/EIC/REF/AIN4/SCOM0PAD0/TC0_9") (pintype "bidirectional"))
    )
    (net (code "37") (name "PA05_AIN5") (class "Default")
      (node (ref "HDR_AD") (pin "5") (pinfunction "5_5") (pintype "passive"))
      (node (ref "MCU") (pin "10") (pinfunction "PA5/EIC/AIN5/SCOM0PAD1/TC0_10") (pintype "bidirectional"))
    )
    (net (code "38") (name "PA6_RFID_SHD") (class "Default")
      (node (ref "HDR_IOH") (pin "1") (pinfunction "1_1") (pintype "passive"))
      (node (ref "MCU") (pin "11") (pinfunction "PA6/EIC/AIN6/SCOM0PAD2/TC1_11") (pintype "bidirectional"))
      (node (ref "RFA") (pin "14") (pinfunction "SHD_14") (pintype "input"))
    )
    (net (code "39") (name "PA7_RFID_SHD2") (class "Default")
      (node (ref "HDR_IOH") (pin "2") (pinfunction "2_2") (pintype "passive"))
      (node (ref "MCU") (pin "12") (pinfunction "PA7/EIC/AIN7/SCOM0PAD3/TC1_12") (pintype "bidirectional"))
      (node (ref "RFB") (pin "14") (pinfunction "SHD_14") (pintype "input"))
    )
    (net (code "40") (name "PA08_TCC0-W0_PA8") (class "Default")
      (node (ref "HDR_IOL") (pin "3") (pinfunction "3_3") (pintype "passive"))
      (node (ref "MCU") (pin "13") (pinfunction "PA8/I2C/AIN16/SCOM2PAD0+/TC0_13") (pintype "bidirectional"))
      (node (ref "MEM") (pin "4") (pinfunction "CS_4") (pintype "bidirectional"))
    )
    (net (code "41") (name "PA09_TCC0-W1_PA9") (class "Default")
      (node (ref "HDR_IOL") (pin "4") (pinfunction "4_4") (pintype "passive"))
      (node (ref "MCU") (pin "14") (pinfunction "PA9/I2C/EIC/AIN17/SCOM2PAD1+/TC0_14") (pintype "bidirectional"))
    )
    (net (code "42") (name "PA10_TCC0-W2_PA10") (class "Default")
      (node (ref "HDR_IOL") (pin "2") (pinfunction "2_2") (pintype "passive"))
      (node (ref "MCU") (pin "15") (pinfunction "PA10/EIC/AIN18/SCOM2PAD2+/TC1_15") (pintype "bidirectional"))
    )
    (net (code "43") (name "PA11_TCC0-W3_PA11") (class "Default")
      (node (ref "HDR_IOL") (pin "1") (pinfunction "1_1") (pintype "passive"))
      (node (ref "MCU") (pin "16") (pinfunction "PA11/EIC/AIN19/SCOM2PAD3+/TC1_16") (pintype "bidirectional"))
    )
    (net (code "44") (name "PA13") (class "Default")
      (node (ref "HDR_IOL") (pin "8") (pinfunction "8_8") (pintype "passive"))
      (node (ref "MCU") (pin "22") (pinfunction "PA13/I2C/EIC/SCOM2PAD1+/TC2_22") (pintype "bidirectional"))
    )
    (net (code "45") (name "PA14_TCC0-W4") (class "Default")
      (node (ref "HDR_IOL") (pin "5") (pinfunction "5_5") (pintype "passive"))
      (node (ref "MCU") (pin "23") (pinfunction "PA14/XIN/EIC/SCOM2PAD2+/TC3_23") (pintype "bidirectional"))
    )
    (net (code "46") (name "PA15_TCC0-W5") (class "Default")
      (node (ref "HDR_IOL") (pin "6") (pinfunction "6_6") (pintype "passive"))
      (node (ref "MCU") (pin "24") (pinfunction "PA15/XOUT/EIC/SCOM2PAD3+/TC3_24") (pintype "bidirectional"))
    )
    (net (code "47") (name "PA16_MOSI") (class "Default")
      (node (ref "HDR_IOH") (pin "4") (pinfunction "4_4") (pintype "passive"))
      (node (ref "MCU") (pin "25") (pinfunction "PA16/I2C/EIC/SCOM1PAD0+/TC2_25") (pintype "bidirectional"))
    )
    (net (code "48") (name "PA17_SCK") (class "Default")
      (node (ref "HDR_IOH") (pin "6") (pinfunction "6_6") (pintype "passive"))
      (node (ref "MCU") (pin "26") (pinfunction "PA17/I2C/EIC/SCOM1PAD1+/TC2_26") (pintype "bidirectional"))
    )
    (net (code "49") (name "PA18_SS") (class "Default")
      (node (ref "HDR_IOH") (pin "3") (pinfunction "3_3") (pintype "passive"))
      (node (ref "MCU") (pin "27") (pinfunction "PA18/EIC/SCOM1PAD2+/TC3_27") (pintype "bidirectional"))
    )
    (net (code "50") (name "PA19_MISO") (class "Default")
      (node (ref "HDR_IOH") (pin "5") (pinfunction "5_5") (pintype "passive"))
      (node (ref "MCU") (pin "28") (pinfunction "PA19/EIC/SCOM1PAD3+/TC3_28") (pintype "bidirectional"))
    )
    (net (code "51") (name "PA20_TCC0-W6") (class "Default")
      (node (ref "HDR_IOL") (pin "7") (pinfunction "7_7") (pintype "passive"))
      (node (ref "MCU") (pin "29") (pinfunction "PA20/EIC/SCOM5PAD2+_29") (pintype "bidirectional"))
    )
    (net (code "52") (name "PA21_INT&SDCS") (class "Default")
      (node (ref "MCU") (pin "30") (pinfunction "PA21/EIC/SCOM5PAD3+_30") (pintype "bidirectional"))
      (node (ref "RP_INT") (pin "1") (pinfunction "1_1") (pintype "passive"))
      (node (ref "RTC") (pin "P$3") (pinfunction "CLK/INT_P$3") (pintype "output"))
      (node (ref "SD") (pin "1") (pinfunction "CS_1") (pintype "input"))
    )
    (net (code "53") (name "PA22_SDA") (class "Default")
      (node (ref "HDR_IOH") (pin "9") (pinfunction "9_9") (pintype "passive"))
      (node (ref "MCU") (pin "31") (pinfunction "PA22/I2C/EIC/SCOM5PAD0+/TC4_31") (pintype "bidirectional"))
      (node (ref "RP_SDA") (pin "1") (pinfunction "1_1") (pintype "passive"))
      (node (ref "RTC") (pin "P$5") (pinfunction "SDA_P$5") (pintype "bidirectional"))
    )
    (net (code "54") (name "PA23_SCL") (class "Default")
      (node (ref "HDR_IOH") (pin "10") (pinfunction "10_10") (pintype "passive"))
      (node (ref "MCU") (pin "32") (pinfunction "PA23/I2C/EIC/SCOM5PAD1+/TC4_32") (pintype "bidirectional"))
      (node (ref "RP_SCL") (pin "1") (pinfunction "1_1") (pintype "passive"))
      (node (ref "RTC") (pin "P$4") (pinfunction "SCL_P$4") (pintype "bidirectional"))
    )
    (net (code "55") (name "PA27_TX_LED") (class "Default")
      (node (ref "MCU") (pin "39") (pinfunction "PA27/EIC_39") (pintype "bidirectional"))
      (node (ref "R1") (pin "2") (pinfunction "2_2") (pintype "passive"))
    )
    (net (code "56") (name "PA28_2FETS") (class "Default")
      (node (ref "MCU") (pin "41") (pinfunction "PA28/EIC_41") (pintype "bidirectional"))
      (node (ref "R3") (pin "1") (pinfunction "1_1") (pintype "passive"))
      (node (ref "T_SD") (pin "1") (pinfunction "G_1") (pintype "passive"))
    )
    (net (code "57") (name "PA30_SWCLK") (class "Default")
      (node (ref "ICSP10") (pin "4") (pinfunction "4_4") (pintype "passive"))
      (node (ref "MCU") (pin "45") (pinfunction "PA30/EIC/SCOM1PAD2/TC1_45") (pintype "bidirectional"))
    )
    (net (code "58") (name "PA31_SWDIO") (class "Default")
      (node (ref "ICSP10") (pin "2") (pinfunction "2_2") (pintype "passive"))
      (node (ref "MCU") (pin "46") (pinfunction "PA31/EIC/SCOM1PAD3/TC1_46") (pintype "bidirectional"))
    )
    (net (code "59") (name "PB02") (class "Default")
      (node (ref "HDR_AD") (pin "6") (pinfunction "6_6") (pintype "passive"))
      (node (ref "MCU") (pin "47") (pinfunction "PB2/EIC/AIN10/SCOM5PAD0_47") (pintype "bidirectional"))
    )
    (net (code "60") (name "PB03_RFIDIN") (class "Default")
      (node (ref "MCU") (pin "48") (pinfunction "PB3/EIC/AIN11/SCOM5PAD1_48") (pintype "bidirectional"))
      (node (ref "RFA") (pin "13") (pinfunction "DMOD_OUT_13") (pintype "output"))
      (node (ref "RFB") (pin "13") (pinfunction "DMOD_OUT_13") (pintype "output"))
    )
    (net (code "61") (name "PB08_AIN2") (class "Default")
      (node (ref "HDR_AD") (pin "2") (pinfunction "2_2") (pintype "passive"))
      (node (ref "MCU") (pin "7") (pinfunction "PB8/EIC/AIN2/SCOM4PAD0/TC4_7") (pintype "bidirectional"))
    )
    (net (code "62") (name "PB09_AIN3") (class "Default")
      (node (ref "HDR_AD") (pin "3") (pinfunction "3_3") (pintype "passive"))
      (node (ref "MCU") (pin "8") (pinfunction "PB9/EIC/AIN3/SCOM4PAD1//TC4_8") (pintype "bidirectional"))
    )
    (net (code "63") (name "PB10_S4_SPI_MOSI") (class "Default")
      (node (ref "ICSP6") (pin "4") (pinfunction "4_4") (pintype "passive"))
      (node (ref "MCU") (pin "19") (pinfunction "PB10/EIC/SCOM4PAD2/TC5_19") (pintype "bidirectional"))
      (node (ref "MEM") (pin "1") (pinfunction "SI_1") (pintype "bidirectional"))
      (node (ref "SD") (pin "2") (pinfunction "DATA_IN_2") (pintype "input"))
    )
    (net (code "64") (name "PB11_S4_SPI_SCK") (class "Default")
      (node (ref "ICSP6") (pin "3") (pinfunction "3_3") (pintype "passive"))
      (node (ref "MCU") (pin "20") (pinfunction "PB11/EIC/SCOM4PAD3/TC5_20") (pintype "bidirectional"))
      (node (ref "MEM") (pin "2") (pinfunction "SCK_2") (pintype "bidirectional"))
      (node (ref "SD") (pin "5") (pinfunction "SCLK_5") (pintype "input"))
    )
    (net (code "65") (name "PB12_S4_SPI_MISO") (class "Default")
      (node (ref "ICSP6") (pin "1") (pinfunction "1_1") (pintype "passive"))
      (node (ref "MCU") (pin "21") (pinfunction "PA12/I2C/EIC/SCOM2PAD0+/TC2_21") (pintype "bidirectional"))
      (node (ref "MEM") (pin "8") (pinfunction "SO_8") (pintype "bidirectional"))
      (node (ref "SD") (pin "7") (pinfunction "DATA_OUT_7") (pintype "output"))
    )
    (net (code "66") (name "PB22_DEBUG_TX") (class "Default")
      (node (ref "MCU") (pin "37") (pinfunction "PB22/EIC/SCOM5PAD2_37") (pintype "bidirectional"))
      (node (ref "TP2") (pin "TP") (pinfunction "TP_TP") (pintype "input"))
    )
    (net (code "67") (name "PB23_DEBUG_RX") (class "Default")
      (node (ref "MCU") (pin "38") (pinfunction "PB23/EIC/SCOM5PAD3_38") (pintype "bidirectional"))
      (node (ref "TP1") (pin "TP") (pinfunction "TP_TP") (pintype "input"))
    )
    (net (code "68") (name "RESET") (class "Default")
      (node (ref "D1") (pin "A") (pinfunction "A_A") (pintype "passive"))
      (node (ref "HDR_POWER") (pin "3") (pinfunction "3_3") (pintype "passive"))
      (node (ref "ICSP10") (pin "10") (pinfunction "10_10") (pintype "passive"))
      (node (ref "ICSP6") (pin "5") (pinfunction "5_5") (pintype "passive"))
      (node (ref "R2") (pin "2") (pinfunction "2_2") (pintype "passive"))
      (node (ref "R4") (pin "1") (pinfunction "1_1") (pintype "passive"))
      (node (ref "RESET") (pin "3") (pinfunction "3_3") (pintype "passive"))
      (node (ref "RESET") (pin "4") (pinfunction "4_4") (pintype "passive"))
    )
    (net (code "69") (name "TARGET_RESET") (class "Default")
      (node (ref "C8") (pin "1") (pinfunction "1_1") (pintype "passive"))
      (node (ref "MCU") (pin "40") (pinfunction "RESETN_40") (pintype "bidirectional"))
      (node (ref "R2") (pin "1") (pinfunction "1_1") (pintype "passive"))
    )
    (net (code "70") (name "TARGET_USB_N") (class "Default")
      (node (ref "MCU") (pin "33") (pinfunction "PA24/EIC/SCOM3PAD2+/TC5_33") (pintype "bidirectional"))
      (node (ref "USB") (pin "D-") (pinfunction "D-_D-") (pintype "bidirectional"))
      (node (ref "Z6") (pin "2") (pinfunction "P$2_2") (pintype "bidirectional"))
    )
    (net (code "71") (name "TARGET_USB_P") (class "Default")
      (node (ref "MCU") (pin "34") (pinfunction "PA25/EIC/SCOM3PAD3+/TC5_34") (pintype "bidirectional"))
      (node (ref "USB") (pin "D+") (pinfunction "D+_D+") (pintype "bidirectional"))
      (node (ref "Z5") (pin "2") (pinfunction "P$2_2") (pintype "bidirectional"))
    )
    (net (code "72") (name "VDDCORE") (class "Default")
      (node (ref "C11") (pin "1") (pinfunction "1_1") (pintype "passive"))
      (node (ref "MCU") (pin "43") (pinfunction "VDDCORE1_43") (pintype "input"))
    )
    (net (code "73") (name "V_IN") (class "Default")
      (node (ref "C5V") (pin "1") (pinfunction "1_1") (pintype "passive"))
      (node (ref "CBLKA") (pin "1") (pinfunction "1_1") (pintype "passive"))
      (node (ref "CBLKB") (pin "1") (pinfunction "1_1") (pintype "passive"))
      (node (ref "CE1") (pin "+") (pinfunction "+_+") (pintype "passive"))
      (node (ref "CE2") (pin "+") (pinfunction "+_+") (pintype "passive"))
      (node (ref "CE3") (pin "+") (pinfunction "+_+") (pintype "passive"))
      (node (ref "CXA") (pin "2") (pinfunction "2_2") (pintype "passive"))
      (node (ref "CXB") (pin "2") (pinfunction "2_2") (pintype "passive"))
      (node (ref "HDR_POWER") (pin "5") (pinfunction "5_5") (pintype "passive"))
      (node (ref "HDR_POWER") (pin "8") (pinfunction "8_8") (pintype "passive"))
      (node (ref "ICSP6") (pin "2") (pinfunction "2_2") (pintype "passive"))
      (node (ref "RFA") (pin "4") (pinfunction "DVDD_4") (pintype "power_in"))
      (node (ref "RFA") (pin "7") (pinfunction "VDD_7") (pintype "power_in"))
      (node (ref "RFB") (pin "4") (pinfunction "DVDD_4") (pintype "power_in"))
      (node (ref "RFB") (pin "7") (pinfunction "VDD_7") (pintype "power_in"))
      (node (ref "SW1") (pin "P$3") (pinfunction "P_P$3") (pintype "passive"))
      (node (ref "VDIV2") (pin "2") (pinfunction "2_2") (pintype "passive"))
      (node (ref "VREG") (pin "1") (pinfunction "VIN_1") (pintype "power_in"))
      (node (ref "VREG") (pin "3") (pinfunction "EN_3") (pintype "input"))
    )
    (net (code "74") (name "XUSB") (class "Default")
      (node (ref "C7") (pin "1") (pinfunction "1_1") (pintype "passive"))
      (node (ref "SW1") (pin "P$5") (pinfunction "S_P$5") (pintype "passive"))
      (node (ref "USB") (pin "VBUS") (pinfunction "VBUS_VBUS") (pintype "bidirectional"))
    )
    (net (code "75") (name "unconnected-(HDR_POWER-Pad1)") (class "Default")
      (node (ref "HDR_POWER") (pin "1") (pinfunction "1_1") (pintype "passive"))
    )
    (net (code "76") (name "unconnected-(ICSP10-Pad6)") (class "Default")
      (node (ref "ICSP10") (pin "6") (pinfunction "6_6") (pintype "passive"))
    )
    (net (code "77") (name "unconnected-(ICSP10-Pad7)") (class "Default")
      (node (ref "ICSP10") (pin "7") (pinfunction "7_7") (pintype "passive"))
    )
    (net (code "78") (name "unconnected-(ICSP10-Pad8)") (class "Default")
      (node (ref "ICSP10") (pin "8") (pinfunction "8_8") (pintype "passive"))
    )
    (net (code "79") (name "unconnected-(RFA-RDY{slash}CLK-Pad2)") (class "Default")
      (node (ref "RFA") (pin "2") (pinfunction "RDY/CLK_2") (pintype "output"))
    )
    (net (code "80") (name "unconnected-(RFB-RDY{slash}CLK-Pad2)") (class "Default")
      (node (ref "RFB") (pin "2") (pinfunction "RDY/CLK_2") (pintype "output"))
    )
    (net (code "81") (name "unconnected-(RTC-CAP_RC-PadP$2)") (class "Default")
      (node (ref "RTC") (pin "P$2") (pinfunction "CAP_RC_P$2") (pintype "bidirectional"))
    )
    (net (code "82") (name "unconnected-(RTC-RST-PadP$10)") (class "Default")
      (node (ref "RTC") (pin "P$10") (pinfunction "RST_P$10") (pintype "bidirectional"))
    )
    (net (code "83") (name "unconnected-(SD-CARD_DETECT-PadCD)") (class "Default")
      (node (ref "SD") (pin "CD") (pinfunction "CARD_DETECT_CD") (pintype "passive"))
    )
    (net (code "84") (name "unconnected-(SD-DAT1-Pad8)") (class "Default")
      (node (ref "SD") (pin "8") (pinfunction "DAT1_8") (pintype "bidirectional"))
    )
    (net (code "85") (name "unconnected-(SD-DAT2-Pad9)") (class "Default")
      (node (ref "SD") (pin "9") (pinfunction "DAT2_9") (pintype "bidirectional"))
    )
    (net (code "86") (name "unconnected-(SD-WRITE_PROTECT-PadWP)") (class "Default")
      (node (ref "SD") (pin "WP") (pinfunction "WRITE_PROTECT_WP") (pintype "passive"))
    )
    (net (code "87") (name "unconnected-(SW1-O1-PadP$2)") (class "Default")
      (node (ref "SW1") (pin "P$2") (pinfunction "O1_P$2") (pintype "passive"))
    )
    (net (code "88") (name "unconnected-(SW1-P1-PadP$4)") (class "Default")
      (node (ref "SW1") (pin "P$4") (pinfunction "P1_P$4") (pintype "passive"))
    )
    (net (code "89") (name "unconnected-(SW1-S1-PadP$6)") (class "Default")
      (node (ref "SW1") (pin "P$6") (pinfunction "S1_P$6") (pintype "passive"))
    )
    (net (code "90") (name "unconnected-(USB-PadID)") (class "Default")
      (node (ref "USB") (pin "ID") (pinfunction "ID_ID") (pintype "bidirectional"))
    )
  )
)
